# Sheet8.net
KiCad netlist of a schematic drawn in Altium Designer
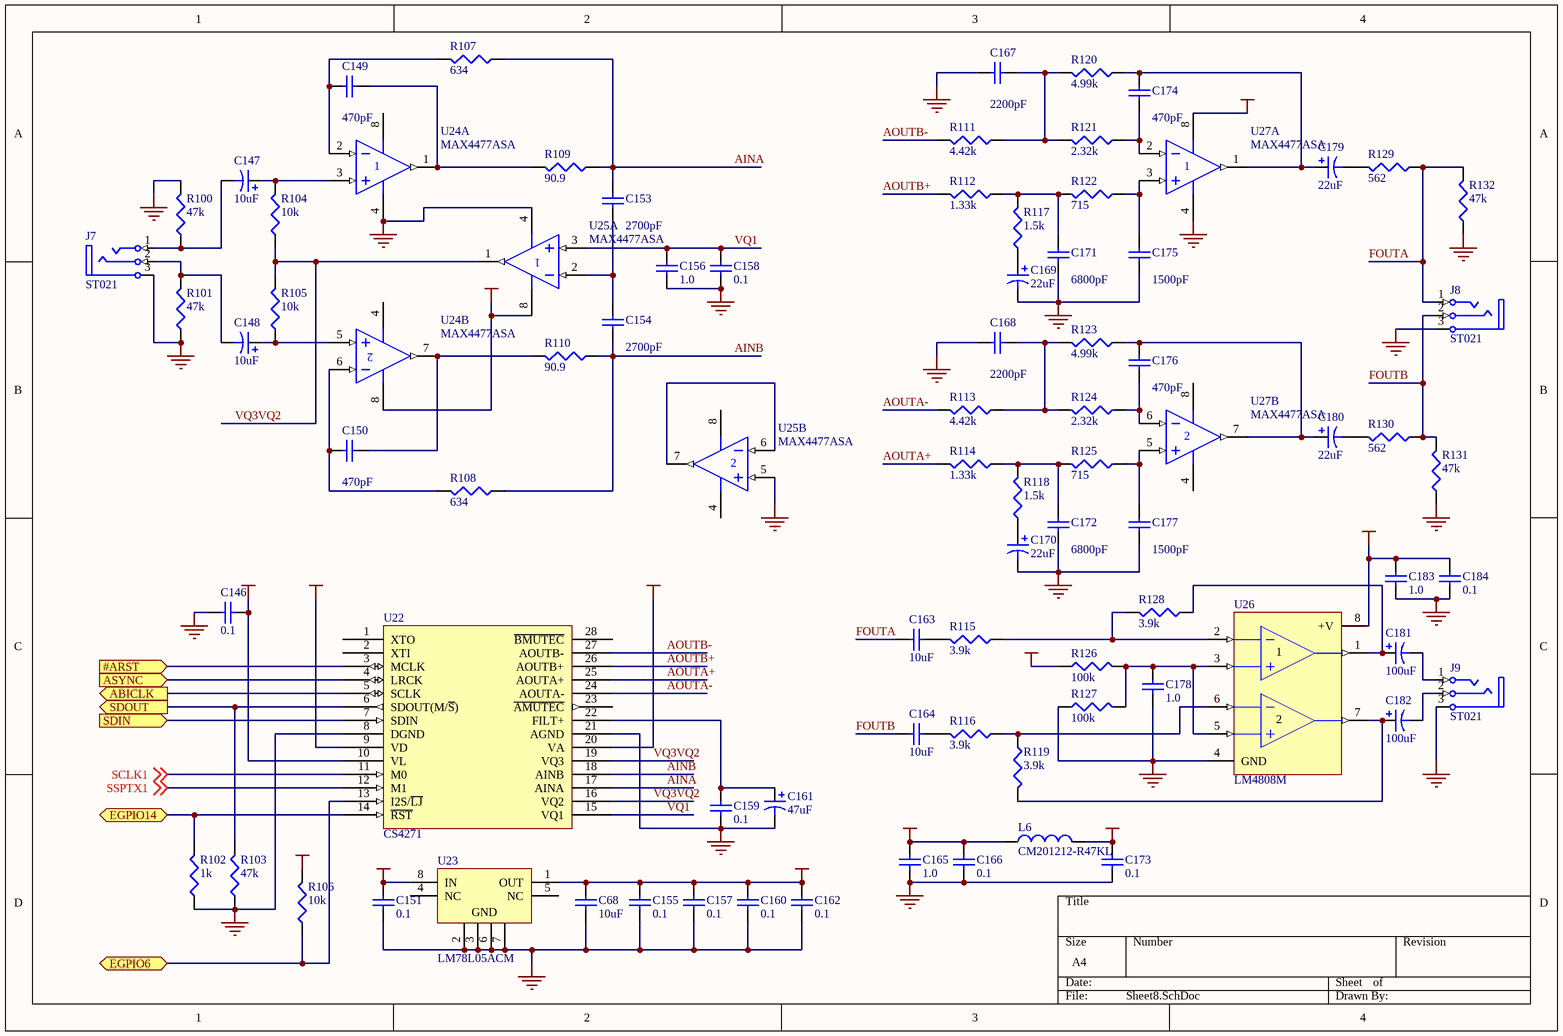
[diagram p0: Sheet8.SchDoc]

(export (version "E")
  (design (tool "Eeschema 10.0.6"))
  (components
    (comp (ref "C68")
      (value "10uF")
      (footprint "1206")
      (description "Ceramic Chip Capacitor - Standard")
      (fields (field (name "PUBLISHER") "Altium Limited"))
      (libsource (lib "KEMET Chip Capacitor") (part "C1206"))
    )
    (comp (ref "C146")
      (value "0.1")
      (footprint "0603")
      (description "Ceramic Chip Capacitor - Standard")
      (fields (field (name "PUBLISHER") "Altium Limited"))
      (libsource (lib "KEMET Chip Capacitor") (part "C0603"))
    )
    (comp (ref "C147")
      (value "10uF")
      (footprint "CAPPR1.5-4x5")
      (description "Polarized Capacitor (Radial)")
      (fields (field (name "PUBLISHER") "Altium Limited"))
      (libsource (lib "Miscellaneous Devices") (part "Cap Pol1"))
    )
    (comp (ref "C148")
      (value "10uF")
      (footprint "CAPPR1.5-4x5")
      (description "Polarized Capacitor (Radial)")
      (fields (field (name "PUBLISHER") "Altium Limited"))
      (libsource (lib "Miscellaneous Devices") (part "Cap Pol1"))
    )
    (comp (ref "C149")
      (value "470pF")
      (footprint "0603")
      (description "Ceramic Chip Capacitor - Standard")
      (fields (field (name "PUBLISHER") "Altium Limited"))
      (libsource (lib "KEMET Chip Capacitor") (part "C0603"))
    )
    (comp (ref "C150")
      (value "470pF")
      (footprint "0603")
      (description "Ceramic Chip Capacitor - Standard")
      (fields (field (name "PUBLISHER") "Altium Limited"))
      (libsource (lib "KEMET Chip Capacitor") (part "C0603"))
    )
    (comp (ref "C151")
      (value "0.1")
      (footprint "0603")
      (description "Ceramic Chip Capacitor - Standard")
      (fields (field (name "PUBLISHER") "Altium Limited"))
      (libsource (lib "KEMET Chip Capacitor") (part "C0603"))
    )
    (comp (ref "C153")
      (value "2700pF")
      (footprint "0603")
      (description "Ceramic Chip Capacitor - Standard")
      (fields (field (name "PUBLISHER") "Altium Limited"))
      (libsource (lib "KEMET Chip Capacitor") (part "C0603"))
    )
    (comp (ref "C154")
      (value "2700pF")
      (footprint "0603")
      (description "Ceramic Chip Capacitor - Standard")
      (fields (field (name "PUBLISHER") "Altium Limited"))
      (libsource (lib "KEMET Chip Capacitor") (part "C0603"))
    )
    (comp (ref "C155")
      (value "0.1")
      (footprint "0603")
      (description "Ceramic Chip Capacitor - Standard")
      (fields (field (name "PUBLISHER") "Altium Limited"))
      (libsource (lib "KEMET Chip Capacitor") (part "C0603"))
    )
    (comp (ref "C156")
      (value "1.0")
      (footprint "0603")
      (description "Ceramic Chip Capacitor - Standard")
      (fields (field (name "PUBLISHER") "Altium Limited"))
      (libsource (lib "KEMET Chip Capacitor") (part "C0603"))
    )
    (comp (ref "C157")
      (value "0.1")
      (footprint "0603")
      (description "Ceramic Chip Capacitor - Standard")
      (fields (field (name "PUBLISHER") "Altium Limited"))
      (libsource (lib "KEMET Chip Capacitor") (part "C0603"))
    )
    (comp (ref "C158")
      (value "0.1")
      (footprint "0603")
      (description "Ceramic Chip Capacitor - Standard")
      (fields (field (name "PUBLISHER") "Altium Limited"))
      (libsource (lib "KEMET Chip Capacitor") (part "C0603"))
    )
    (comp (ref "C159")
      (value "0.1")
      (footprint "0603")
      (description "Ceramic Chip Capacitor - Standard")
      (fields (field (name "PUBLISHER") "Altium Limited"))
      (libsource (lib "KEMET Chip Capacitor") (part "C0603"))
    )
    (comp (ref "C160")
      (value "0.1")
      (footprint "0603")
      (description "Ceramic Chip Capacitor - Standard")
      (fields (field (name "PUBLISHER") "Altium Limited"))
      (libsource (lib "KEMET Chip Capacitor") (part "C0603"))
    )
    (comp (ref "C161")
      (value "47uF")
      (footprint "CAPPR1.5-4x5")
      (description "Polarized Capacitor (Radial)")
      (fields (field (name "PUBLISHER") "Altium Limited"))
      (libsource (lib "Miscellaneous Devices") (part "Cap Pol1"))
    )
    (comp (ref "C162")
      (value "0.1")
      (footprint "0603")
      (description "Ceramic Chip Capacitor - Standard")
      (fields (field (name "PUBLISHER") "Altium Limited"))
      (libsource (lib "KEMET Chip Capacitor") (part "C0603"))
    )
    (comp (ref "C163")
      (value "10uF")
      (footprint "1206")
      (description "Ceramic Chip Capacitor - Standard")
      (fields (field (name "PUBLISHER") "Altium Limited"))
      (libsource (lib "KEMET Chip Capacitor") (part "C1206"))
    )
    (comp (ref "C164")
      (value "10uF")
      (footprint "1206")
      (description "Ceramic Chip Capacitor - Standard")
      (fields (field (name "PUBLISHER") "Altium Limited"))
      (libsource (lib "KEMET Chip Capacitor") (part "C1206"))
    )
    (comp (ref "C165")
      (value "1.0")
      (footprint "0603")
      (description "Ceramic Chip Capacitor - Standard")
      (fields (field (name "PUBLISHER") "Altium Limited"))
      (libsource (lib "KEMET Chip Capacitor") (part "C0603"))
    )
    (comp (ref "C166")
      (value "0.1")
      (footprint "0603")
      (description "Ceramic Chip Capacitor - Standard")
      (fields (field (name "PUBLISHER") "Altium Limited"))
      (libsource (lib "KEMET Chip Capacitor") (part "C0603"))
    )
    (comp (ref "C167")
      (value "2200pF")
      (footprint "0603")
      (description "Ceramic Chip Capacitor - Standard")
      (fields (field (name "PUBLISHER") "Altium Limited"))
      (libsource (lib "KEMET Chip Capacitor") (part "C0603"))
    )
    (comp (ref "C168")
      (value "2200pF")
      (footprint "0603")
      (description "Ceramic Chip Capacitor - Standard")
      (fields (field (name "PUBLISHER") "Altium Limited"))
      (libsource (lib "KEMET Chip Capacitor") (part "C0603"))
    )
    (comp (ref "C169")
      (value "22uF")
      (footprint "CAPPR1.5-4x5")
      (description "Polarized Capacitor (Radial)")
      (fields (field (name "PUBLISHER") "Altium Limited"))
      (libsource (lib "Miscellaneous Devices") (part "Cap Pol1"))
    )
    (comp (ref "C170")
      (value "22uF")
      (footprint "CAPPR1.5-4x5")
      (description "Polarized Capacitor (Radial)")
      (fields (field (name "PUBLISHER") "Altium Limited"))
      (libsource (lib "Miscellaneous Devices") (part "Cap Pol1"))
    )
    (comp (ref "C171")
      (value "6800pF")
      (footprint "0603")
      (description "Ceramic Chip Capacitor - Standard")
      (fields (field (name "PUBLISHER") "Altium Limited"))
      (libsource (lib "KEMET Chip Capacitor") (part "C0603"))
    )
    (comp (ref "C172")
      (value "6800pF")
      (footprint "0603")
      (description "Ceramic Chip Capacitor - Standard")
      (fields (field (name "PUBLISHER") "Altium Limited"))
      (libsource (lib "KEMET Chip Capacitor") (part "C0603"))
    )
    (comp (ref "C173")
      (value "0.1")
      (footprint "0603")
      (description "Ceramic Chip Capacitor - Standard")
      (fields (field (name "PUBLISHER") "Altium Limited"))
      (libsource (lib "KEMET Chip Capacitor") (part "C0603"))
    )
    (comp (ref "C174")
      (value "470pF")
      (footprint "0603")
      (description "Ceramic Chip Capacitor - Standard")
      (fields (field (name "PUBLISHER") "Altium Limited"))
      (libsource (lib "KEMET Chip Capacitor") (part "C0603"))
    )
    (comp (ref "C175")
      (value "1500pF")
      (footprint "0603")
      (description "Ceramic Chip Capacitor - Standard")
      (fields (field (name "PUBLISHER") "Altium Limited"))
      (libsource (lib "KEMET Chip Capacitor") (part "C0603"))
    )
    (comp (ref "C176")
      (value "470pF")
      (footprint "0603")
      (description "Ceramic Chip Capacitor - Standard")
      (fields (field (name "PUBLISHER") "Altium Limited"))
      (libsource (lib "KEMET Chip Capacitor") (part "C0603"))
    )
    (comp (ref "C177")
      (value "1500pF")
      (footprint "0603")
      (description "Ceramic Chip Capacitor - Standard")
      (fields (field (name "PUBLISHER") "Altium Limited"))
      (libsource (lib "KEMET Chip Capacitor") (part "C0603"))
    )
    (comp (ref "C178")
      (value "1.0")
      (footprint "0603")
      (description "Ceramic Chip Capacitor - Standard")
      (fields (field (name "PUBLISHER") "Altium Limited"))
      (libsource (lib "KEMET Chip Capacitor") (part "C0603"))
    )
    (comp (ref "C179")
      (value "22uF")
      (footprint "CAPPR1.5-4x5")
      (description "Polarized Capacitor (Radial)")
      (fields (field (name "PUBLISHER") "Altium Limited"))
      (libsource (lib "Miscellaneous Devices") (part "Cap Pol1"))
    )
    (comp (ref "C180")
      (value "22uF")
      (footprint "CAPPR1.5-4x5")
      (description "Polarized Capacitor (Radial)")
      (fields (field (name "PUBLISHER") "Altium Limited"))
      (libsource (lib "Miscellaneous Devices") (part "Cap Pol1"))
    )
    (comp (ref "C181")
      (value "100uF")
      (footprint "CAPPR1.5-4x5")
      (description "Polarized Capacitor (Radial)")
      (fields (field (name "PUBLISHER") "Altium Limited"))
      (libsource (lib "Miscellaneous Devices") (part "Cap Pol1"))
    )
    (comp (ref "C182")
      (value "100uF")
      (footprint "CAPPR1.5-4x5")
      (description "Polarized Capacitor (Radial)")
      (fields (field (name "PUBLISHER") "Altium Limited"))
      (libsource (lib "Miscellaneous Devices") (part "Cap Pol1"))
    )
    (comp (ref "C183")
      (value "1.0")
      (footprint "0603")
      (description "Ceramic Chip Capacitor - Standard")
      (fields (field (name "PUBLISHER") "Altium Limited"))
      (libsource (lib "KEMET Chip Capacitor") (part "C0603"))
    )
    (comp (ref "C184")
      (value "0.1")
      (footprint "0603")
      (description "Ceramic Chip Capacitor - Standard")
      (fields (field (name "PUBLISHER") "Altium Limited"))
      (libsource (lib "KEMET Chip Capacitor") (part "C0603"))
    )
    (comp (ref "J7")
      (value "ST021")
      (footprint "ST023")
      (description "3.5\" jack")
      (libsource (lib "*") (part "PhoneJack"))
    )
    (comp (ref "J8")
      (value "ST021")
      (footprint "ST023")
      (description "3.5\" jack")
      (libsource (lib "*") (part "PhoneJack"))
    )
    (comp (ref "J9")
      (value "ST021")
      (footprint "ST023")
      (description "3.5\" jack")
      (libsource (lib "*") (part "PhoneJack"))
    )
    (comp (ref "L6")
      (value "CM201212-R47KL")
      (footprint "INDC2012-0805")
      (description "Inductor")
      (fields (field (name "PUBLISHER") "Altium Limited"))
      (libsource (lib "Miscellaneous Devices") (part "Inductor"))
    )
    (comp (ref "R100")
      (value "47k")
      (footprint "CR1608-0603")
      (description "Resistor")
      (fields (field (name "PUBLISHER") "Altium Limited"))
      (libsource (lib "Miscellaneous Devices") (part "Res3"))
    )
    (comp (ref "R101")
      (value "47k")
      (footprint "CR1608-0603")
      (description "Resistor")
      (fields (field (name "PUBLISHER") "Altium Limited"))
      (libsource (lib "Miscellaneous Devices") (part "Res3"))
    )
    (comp (ref "R102")
      (value "1k")
      (footprint "CR1608-0603")
      (description "Resistor")
      (fields (field (name "PUBLISHER") "Altium Limited"))
      (libsource (lib "Miscellaneous Devices") (part "Res3"))
    )
    (comp (ref "R103")
      (value "47k")
      (footprint "CR1608-0603")
      (description "Resistor")
      (fields (field (name "PUBLISHER") "Altium Limited"))
      (libsource (lib "Miscellaneous Devices") (part "Res3"))
    )
    (comp (ref "R104")
      (value "10k")
      (footprint "CR1608-0603")
      (description "Resistor")
      (fields (field (name "PUBLISHER") "Altium Limited"))
      (libsource (lib "Miscellaneous Devices") (part "Res3"))
    )
    (comp (ref "R105")
      (value "10k")
      (footprint "CR1608-0603")
      (description "Resistor")
      (fields (field (name "PUBLISHER") "Altium Limited"))
      (libsource (lib "Miscellaneous Devices") (part "Res3"))
    )
    (comp (ref "R106")
      (value "10k")
      (footprint "CR1608-0603")
      (description "Resistor")
      (fields (field (name "PUBLISHER") "Altium Limited"))
      (libsource (lib "Miscellaneous Devices") (part "Res3"))
    )
    (comp (ref "R107")
      (value "634")
      (footprint "CR1608-0603")
      (description "Resistor")
      (fields (field (name "PUBLISHER") "Altium Limited"))
      (libsource (lib "Miscellaneous Devices") (part "Res3"))
    )
    (comp (ref "R108")
      (value "634")
      (footprint "CR1608-0603")
      (description "Resistor")
      (fields (field (name "PUBLISHER") "Altium Limited"))
      (libsource (lib "Miscellaneous Devices") (part "Res3"))
    )
    (comp (ref "R109")
      (value "90.9")
      (footprint "CR1608-0603")
      (description "Resistor")
      (fields (field (name "PUBLISHER") "Altium Limited"))
      (libsource (lib "Miscellaneous Devices") (part "Res3"))
    )
    (comp (ref "R110")
      (value "90.9")
      (footprint "CR1608-0603")
      (description "Resistor")
      (fields (field (name "PUBLISHER") "Altium Limited"))
      (libsource (lib "Miscellaneous Devices") (part "Res3"))
    )
    (comp (ref "R111")
      (value "4.42k")
      (footprint "CR1608-0603")
      (description "Resistor")
      (fields (field (name "PUBLISHER") "Altium Limited"))
      (libsource (lib "Miscellaneous Devices") (part "Res3"))
    )
    (comp (ref "R112")
      (value "1.33k")
      (footprint "CR1608-0603")
      (description "Resistor")
      (fields (field (name "PUBLISHER") "Altium Limited"))
      (libsource (lib "Miscellaneous Devices") (part "Res3"))
    )
    (comp (ref "R113")
      (value "4.42k")
      (footprint "CR1608-0603")
      (description "Resistor")
      (fields (field (name "PUBLISHER") "Altium Limited"))
      (libsource (lib "Miscellaneous Devices") (part "Res3"))
    )
    (comp (ref "R114")
      (value "1.33k")
      (footprint "CR1608-0603")
      (description "Resistor")
      (fields (field (name "PUBLISHER") "Altium Limited"))
      (libsource (lib "Miscellaneous Devices") (part "Res3"))
    )
    (comp (ref "R115")
      (value "3.9k")
      (footprint "CR1608-0603")
      (description "Resistor")
      (fields (field (name "PUBLISHER") "Altium Limited"))
      (libsource (lib "Miscellaneous Devices") (part "Res3"))
    )
    (comp (ref "R116")
      (value "3.9k")
      (footprint "CR1608-0603")
      (description "Resistor")
      (fields (field (name "PUBLISHER") "Altium Limited"))
      (libsource (lib "Miscellaneous Devices") (part "Res3"))
    )
    (comp (ref "R117")
      (value "1.5k")
      (footprint "CR1608-0603")
      (description "Resistor")
      (fields (field (name "PUBLISHER") "Altium Limited"))
      (libsource (lib "Miscellaneous Devices") (part "Res3"))
    )
    (comp (ref "R118")
      (value "1.5k")
      (footprint "CR1608-0603")
      (description "Resistor")
      (fields (field (name "PUBLISHER") "Altium Limited"))
      (libsource (lib "Miscellaneous Devices") (part "Res3"))
    )
    (comp (ref "R119")
      (value "3.9k")
      (footprint "CR1608-0603")
      (description "Resistor")
      (fields (field (name "PUBLISHER") "Altium Limited"))
      (libsource (lib "Miscellaneous Devices") (part "Res3"))
    )
    (comp (ref "R120")
      (value "4.99k")
      (footprint "CR1608-0603")
      (description "Resistor")
      (fields (field (name "PUBLISHER") "Altium Limited"))
      (libsource (lib "Miscellaneous Devices") (part "Res3"))
    )
    (comp (ref "R121")
      (value "2.32k")
      (footprint "CR1608-0603")
      (description "Resistor")
      (fields (field (name "PUBLISHER") "Altium Limited"))
      (libsource (lib "Miscellaneous Devices") (part "Res3"))
    )
    (comp (ref "R122")
      (value "715")
      (footprint "CR1608-0603")
      (description "Resistor")
      (fields (field (name "PUBLISHER") "Altium Limited"))
      (libsource (lib "Miscellaneous Devices") (part "Res3"))
    )
    (comp (ref "R123")
      (value "4.99k")
      (footprint "CR1608-0603")
      (description "Resistor")
      (fields (field (name "PUBLISHER") "Altium Limited"))
      (libsource (lib "Miscellaneous Devices") (part "Res3"))
    )
    (comp (ref "R124")
      (value "2.32k")
      (footprint "CR1608-0603")
      (description "Resistor")
      (fields (field (name "PUBLISHER") "Altium Limited"))
      (libsource (lib "Miscellaneous Devices") (part "Res3"))
    )
    (comp (ref "R125")
      (value "715")
      (footprint "CR1608-0603")
      (description "Resistor")
      (fields (field (name "PUBLISHER") "Altium Limited"))
      (libsource (lib "Miscellaneous Devices") (part "Res3"))
    )
    (comp (ref "R126")
      (value "100k")
      (footprint "CR1608-0603")
      (description "Resistor")
      (fields (field (name "PUBLISHER") "Altium Limited"))
      (libsource (lib "Miscellaneous Devices") (part "Res3"))
    )
    (comp (ref "R127")
      (value "100k")
      (footprint "CR1608-0603")
      (description "Resistor")
      (fields (field (name "PUBLISHER") "Altium Limited"))
      (libsource (lib "Miscellaneous Devices") (part "Res3"))
    )
    (comp (ref "R128")
      (value "3.9k")
      (footprint "CR1608-0603")
      (description "Resistor")
      (fields (field (name "PUBLISHER") "Altium Limited"))
      (libsource (lib "Miscellaneous Devices") (part "Res3"))
    )
    (comp (ref "R129")
      (value "562")
      (footprint "CR1608-0603")
      (description "Resistor")
      (fields (field (name "PUBLISHER") "Altium Limited"))
      (libsource (lib "Miscellaneous Devices") (part "Res3"))
    )
    (comp (ref "R130")
      (value "562")
      (footprint "CR1608-0603")
      (description "Resistor")
      (fields (field (name "PUBLISHER") "Altium Limited"))
      (libsource (lib "Miscellaneous Devices") (part "Res3"))
    )
    (comp (ref "R131")
      (value "47k")
      (footprint "CR1608-0603")
      (description "Resistor")
      (fields (field (name "PUBLISHER") "Altium Limited"))
      (libsource (lib "Miscellaneous Devices") (part "Res3"))
    )
    (comp (ref "R132")
      (value "47k")
      (footprint "CR1608-0603")
      (description "Resistor")
      (fields (field (name "PUBLISHER") "Altium Limited"))
      (libsource (lib "Miscellaneous Devices") (part "Res3"))
    )
    (comp (ref "U22")
      (value "CS4271")
      (footprint "TSOP28")
      (description "24-Bit, 192 kHz Stereo Audio CODEC")
      (libsource (lib "CS4271") (part "CS4271"))
    )
    (comp (ref "U23")
      (value "LM78L05ACM")
      (footprint "M08A")
      (description "3-Terminal Positive Regulator")
      (fields (field (name "PUBLISHER") "Altium Limited"))
      (libsource (lib "NSC Power Mgt Voltage Regulator") (part "LM78L05ACM"))
    )
    (comp (ref "U24")
      (value "MAX4477ASA")
      (footprint "NSO8")
      (description "Dual, +1.8V/10µA, SOT23, Beyond-the-Rails Op Amp")
      (fields (field (name "PUBLISHER") "Altium Limited"))
      (libsource (lib "Maxim Operational Amplifier") (part "MAX4242ESA"))
    )
    (comp (ref "U25")
      (value "MAX4477ASA")
      (footprint "NSO8")
      (description "Dual, +1.8V/10µA, SOT23, Beyond-the-Rails Op Amp")
      (fields (field (name "PUBLISHER") "Altium Limited"))
      (libsource (lib "Maxim Operational Amplifier") (part "MAX4242ESA"))
    )
    (comp (ref "U26")
      (value "LM4808M")
      (footprint "M08A")
      (description "Dual 105 mW Headphone Amplifier")
      (libsource (lib "*") (part "LM4808M"))
    )
    (comp (ref "U27")
      (value "MAX4477ASA")
      (footprint "NSO8")
      (description "Dual, +1.8V/10µA, SOT23, Beyond-the-Rails Op Amp")
      (fields (field (name "PUBLISHER") "Altium Limited"))
      (libsource (lib "Maxim Operational Amplifier") (part "MAX4242ESA"))
    )
  )
  (nets
    (net (code "1") (name "/#ARST") (class "Default")
      (node (ref "U22") (pin "3") (pinfunction "MCLK_3") (pintype "bidirectional"))
    )
    (net (code "2") (name "/ABICLK") (class "Default")
      (node (ref "U22") (pin "5") (pinfunction "SCLK_5") (pintype "bidirectional"))
    )
    (net (code "3") (name "/AINA") (class "Default")
      (node (ref "C153") (pin "2") (pinfunction "2_2") (pintype "passive"))
      (node (ref "R107") (pin "1") (pinfunction "1_1") (pintype "passive"))
      (node (ref "R109") (pin "1") (pinfunction "1_1") (pintype "passive"))
      (node (ref "U22") (pin "17") (pinfunction "AINA_17") (pintype "passive"))
    )
    (net (code "4") (name "/AINB") (class "Default")
      (node (ref "C154") (pin "1") (pinfunction "1_1") (pintype "passive"))
      (node (ref "R108") (pin "1") (pinfunction "1_1") (pintype "passive"))
      (node (ref "R110") (pin "1") (pinfunction "1_1") (pintype "passive"))
      (node (ref "U22") (pin "18") (pinfunction "AINB_18") (pintype "passive"))
    )
    (net (code "5") (name "/AOUTA+") (class "Default")
      (node (ref "R114") (pin "2") (pinfunction "2_2") (pintype "passive"))
      (node (ref "U22") (pin "25") (pinfunction "AOUTA+_25") (pintype "passive"))
    )
    (net (code "6") (name "/AOUTA-") (class "Default")
      (node (ref "R113") (pin "2") (pinfunction "2_2") (pintype "passive"))
      (node (ref "U22") (pin "24") (pinfunction "AOUTA-_24") (pintype "passive"))
    )
    (net (code "7") (name "/AOUTB+") (class "Default")
      (node (ref "R112") (pin "2") (pinfunction "2_2") (pintype "passive"))
      (node (ref "U22") (pin "26") (pinfunction "AOUTB+_26") (pintype "passive"))
    )
    (net (code "8") (name "/AOUTB-") (class "Default")
      (node (ref "R111") (pin "2") (pinfunction "2_2") (pintype "passive"))
      (node (ref "U22") (pin "27") (pinfunction "AOUTB-_27") (pintype "passive"))
    )
    (net (code "9") (name "/ASYNC") (class "Default")
      (node (ref "U22") (pin "4") (pinfunction "LRCK_4") (pintype "bidirectional"))
    )
    (net (code "10") (name "/EGPIO6") (class "Default")
      (node (ref "R106") (pin "1") (pinfunction "1_1") (pintype "passive"))
      (node (ref "U22") (pin "13") (pinfunction "I2S/~{LJ}_13") (pintype "input"))
    )
    (net (code "11") (name "/EGPIO14") (class "Default")
      (node (ref "R102") (pin "2") (pinfunction "2_2") (pintype "passive"))
      (node (ref "U22") (pin "14") (pinfunction "~{RST}_14") (pintype "input"))
    )
    (net (code "12") (name "/FOUTA") (class "Default")
      (node (ref "C163") (pin "2") (pinfunction "2_2") (pintype "passive"))
      (node (ref "J8") (pin "1") (pinfunction "T_1") (pintype "input"))
      (node (ref "R129") (pin "1") (pinfunction "1_1") (pintype "passive"))
      (node (ref "R132") (pin "2") (pinfunction "2_2") (pintype "passive"))
    )
    (net (code "13") (name "/FOUTB") (class "Default")
      (node (ref "C164") (pin "2") (pinfunction "2_2") (pintype "passive"))
      (node (ref "J8") (pin "2") (pinfunction "R_2") (pintype "input"))
      (node (ref "R130") (pin "1") (pinfunction "1_1") (pintype "passive"))
      (node (ref "R131") (pin "2") (pinfunction "2_2") (pintype "passive"))
    )
    (net (code "14") (name "/SDIN") (class "Default")
      (node (ref "U22") (pin "7") (pinfunction "SDIN_7") (pintype "input"))
    )
    (net (code "15") (name "/SDOUT") (class "Default")
      (node (ref "R103") (pin "2") (pinfunction "2_2") (pintype "passive"))
      (node (ref "U22") (pin "6") (pinfunction "SDOUT(M/~{S})_6") (pintype "output"))
    )
    (net (code "16") (name "/VQ1") (class "Default")
      (node (ref "C156") (pin "2") (pinfunction "2_2") (pintype "passive"))
      (node (ref "C158") (pin "2") (pinfunction "2_2") (pintype "passive"))
      (node (ref "U22") (pin "15") (pinfunction "VQ1_15") (pintype "passive"))
      (node (ref "U25") (pin "3") (pinfunction "IN+_3") (pintype "input"))
    )
    (net (code "17") (name "/VQ3VQ2") (class "Default")
      (node (ref "R104") (pin "1") (pinfunction "1_1") (pintype "passive"))
      (node (ref "R105") (pin "2") (pinfunction "2_2") (pintype "passive"))
      (node (ref "U22") (pin "16") (pinfunction "VQ2_16") (pintype "passive"))
      (node (ref "U22") (pin "19") (pinfunction "VQ3_19") (pintype "passive"))
      (node (ref "U25") (pin "1") (pinfunction "OUT_1") (pintype "output"))
    )
    (net (code "18") (name "GND") (class "Default")
      (node (ref "C146") (pin "1") (pinfunction "1_1") (pintype "passive"))
      (node (ref "C151") (pin "2") (pinfunction "2_2") (pintype "passive"))
      (node (ref "C155") (pin "2") (pinfunction "2_2") (pintype "passive"))
      (node (ref "C156") (pin "1") (pinfunction "1_1") (pintype "passive"))
      (node (ref "C157") (pin "2") (pinfunction "2_2") (pintype "passive"))
      (node (ref "C158") (pin "1") (pinfunction "1_1") (pintype "passive"))
      (node (ref "C159") (pin "2") (pinfunction "2_2") (pintype "passive"))
      (node (ref "C160") (pin "2") (pinfunction "2_2") (pintype "passive"))
      (node (ref "C161") (pin "2") (pinfunction "2_2") (pintype "passive"))
      (node (ref "C162") (pin "2") (pinfunction "2_2") (pintype "passive"))
      (node (ref "C165") (pin "1") (pinfunction "1_1") (pintype "passive"))
      (node (ref "C166") (pin "2") (pinfunction "2_2") (pintype "passive"))
      (node (ref "C167") (pin "2") (pinfunction "2_2") (pintype "passive"))
      (node (ref "C168") (pin "2") (pinfunction "2_2") (pintype "passive"))
      (node (ref "C169") (pin "2") (pinfunction "2_2") (pintype "passive"))
      (node (ref "C170") (pin "2") (pinfunction "2_2") (pintype "passive"))
      (node (ref "C171") (pin "1") (pinfunction "1_1") (pintype "passive"))
      (node (ref "C172") (pin "1") (pinfunction "1_1") (pintype "passive"))
      (node (ref "C173") (pin "2") (pinfunction "2_2") (pintype "passive"))
      (node (ref "C175") (pin "1") (pinfunction "1_1") (pintype "passive"))
      (node (ref "C177") (pin "1") (pinfunction "1_1") (pintype "passive"))
      (node (ref "C178") (pin "1") (pinfunction "1_1") (pintype "passive"))
      (node (ref "C183") (pin "1") (pinfunction "1_1") (pintype "passive"))
      (node (ref "C184") (pin "2") (pinfunction "2_2") (pintype "passive"))
      (node (ref "C68") (pin "1") (pinfunction "1_1") (pintype "passive"))
      (node (ref "J7") (pin "3") (pinfunction "S_3") (pintype "power_in"))
      (node (ref "J8") (pin "3") (pinfunction "S_3") (pintype "power_in"))
      (node (ref "J9") (pin "3") (pinfunction "S_3") (pintype "power_in"))
      (node (ref "R100") (pin "2") (pinfunction "2_2") (pintype "passive"))
      (node (ref "R101") (pin "1") (pinfunction "1_1") (pintype "passive"))
      (node (ref "R102") (pin "1") (pinfunction "1_1") (pintype "passive"))
      (node (ref "R103") (pin "1") (pinfunction "1_1") (pintype "passive"))
      (node (ref "R127") (pin "1") (pinfunction "1_1") (pintype "passive"))
      (node (ref "R131") (pin "1") (pinfunction "1_1") (pintype "passive"))
      (node (ref "R132") (pin "1") (pinfunction "1_1") (pintype "passive"))
      (node (ref "U22") (pin "21") (pinfunction "AGND_21") (pintype "passive"))
      (node (ref "U22") (pin "8") (pinfunction "DGND_8") (pintype "passive"))
      (node (ref "U23") (pin "2") (pinfunction "GND_2") (pintype "power_in"))
      (node (ref "U23") (pin "3") (pinfunction "GND_3") (pintype "power_in"))
      (node (ref "U23") (pin "6") (pinfunction "GND_6") (pintype "power_in"))
      (node (ref "U23") (pin "7") (pinfunction "GND_7") (pintype "power_in"))
      (node (ref "U24") (pin "4") (pinfunction "VEE_4") (pintype "power_in"))
      (node (ref "U25") (pin "4") (pinfunction "VEE_4") (pintype "power_in"))
      (node (ref "U25") (pin "5") (pinfunction "IN+_5") (pintype "input"))
      (node (ref "U26") (pin "4") (pinfunction "GND_4") (pintype "power_in"))
      (node (ref "U27") (pin "4") (pinfunction "VEE_4") (pintype "power_in"))
    )
    (net (code "19") (name "Net-(C163-Pad1)") (class "Default")
      (node (ref "C163") (pin "1") (pinfunction "1_1") (pintype "passive"))
      (node (ref "R115") (pin "2") (pinfunction "2_2") (pintype "passive"))
    )
    (net (code "20") (name "Net-(C164-Pad1)") (class "Default")
      (node (ref "C164") (pin "1") (pinfunction "1_1") (pintype "passive"))
      (node (ref "R116") (pin "2") (pinfunction "2_2") (pintype "passive"))
    )
    (net (code "21") (name "Net-(C167-Pad1)") (class "Default")
      (node (ref "C167") (pin "1") (pinfunction "1_1") (pintype "passive"))
      (node (ref "R111") (pin "1") (pinfunction "1_1") (pintype "passive"))
      (node (ref "R120") (pin "2") (pinfunction "2_2") (pintype "passive"))
      (node (ref "R121") (pin "2") (pinfunction "2_2") (pintype "passive"))
    )
    (net (code "22") (name "Net-(C168-Pad1)") (class "Default")
      (node (ref "C168") (pin "1") (pinfunction "1_1") (pintype "passive"))
      (node (ref "R113") (pin "1") (pinfunction "1_1") (pintype "passive"))
      (node (ref "R123") (pin "2") (pinfunction "2_2") (pintype "passive"))
      (node (ref "R124") (pin "2") (pinfunction "2_2") (pintype "passive"))
    )
    (net (code "23") (name "Net-(C169-Pad1)") (class "Default")
      (node (ref "C169") (pin "1") (pinfunction "1_1") (pintype "passive"))
      (node (ref "R117") (pin "1") (pinfunction "1_1") (pintype "passive"))
    )
    (net (code "24") (name "Net-(C170-Pad1)") (class "Default")
      (node (ref "C170") (pin "1") (pinfunction "1_1") (pintype "passive"))
      (node (ref "R118") (pin "1") (pinfunction "1_1") (pintype "passive"))
    )
    (net (code "25") (name "Net-(C171-Pad2)") (class "Default")
      (node (ref "C171") (pin "2") (pinfunction "2_2") (pintype "passive"))
      (node (ref "R112") (pin "1") (pinfunction "1_1") (pintype "passive"))
      (node (ref "R117") (pin "2") (pinfunction "2_2") (pintype "passive"))
      (node (ref "R122") (pin "2") (pinfunction "2_2") (pintype "passive"))
    )
    (net (code "26") (name "Net-(C172-Pad2)") (class "Default")
      (node (ref "C172") (pin "2") (pinfunction "2_2") (pintype "passive"))
      (node (ref "R114") (pin "1") (pinfunction "1_1") (pintype "passive"))
      (node (ref "R118") (pin "2") (pinfunction "2_2") (pintype "passive"))
      (node (ref "R125") (pin "2") (pinfunction "2_2") (pintype "passive"))
    )
    (net (code "27") (name "Net-(C178-Pad2)") (class "Default")
      (node (ref "C178") (pin "2") (pinfunction "2_2") (pintype "passive"))
      (node (ref "R126") (pin "2") (pinfunction "2_2") (pintype "passive"))
      (node (ref "R127") (pin "2") (pinfunction "2_2") (pintype "passive"))
      (node (ref "U26") (pin "3") (pinfunction "IN+_3") (pintype "input"))
      (node (ref "U26") (pin "5") (pinfunction "IN+_5") (pintype "input"))
    )
    (net (code "28") (name "Net-(C179-Pad2)") (class "Default")
      (node (ref "C179") (pin "2") (pinfunction "2_2") (pintype "passive"))
      (node (ref "R129") (pin "2") (pinfunction "2_2") (pintype "passive"))
    )
    (net (code "29") (name "Net-(C180-Pad2)") (class "Default")
      (node (ref "C180") (pin "2") (pinfunction "2_2") (pintype "passive"))
      (node (ref "R130") (pin "2") (pinfunction "2_2") (pintype "passive"))
    )
    (net (code "30") (name "Net-(C181-Pad1)") (class "Default")
      (node (ref "C181") (pin "1") (pinfunction "1_1") (pintype "passive"))
      (node (ref "R128") (pin "1") (pinfunction "1_1") (pintype "passive"))
      (node (ref "U26") (pin "1") (pinfunction "OUT_1") (pintype "output"))
    )
    (net (code "31") (name "Net-(C182-Pad1)") (class "Default")
      (node (ref "C182") (pin "1") (pinfunction "1_1") (pintype "passive"))
      (node (ref "R119") (pin "2") (pinfunction "2_2") (pintype "passive"))
      (node (ref "U26") (pin "7") (pinfunction "OUT_7") (pintype "output"))
    )
    (net (code "32") (name "Net-(J7-R)") (class "Default")
      (node (ref "C148") (pin "2") (pinfunction "2_2") (pintype "passive"))
      (node (ref "J7") (pin "2") (pinfunction "R_2") (pintype "input"))
      (node (ref "R101") (pin "2") (pinfunction "2_2") (pintype "passive"))
    )
    (net (code "33") (name "Net-(J7-T)") (class "Default")
      (node (ref "C147") (pin "2") (pinfunction "2_2") (pintype "passive"))
      (node (ref "J7") (pin "1") (pinfunction "T_1") (pintype "input"))
      (node (ref "R100") (pin "1") (pinfunction "1_1") (pintype "passive"))
    )
    (net (code "34") (name "Net-(J9-R)") (class "Default")
      (node (ref "C182") (pin "2") (pinfunction "2_2") (pintype "passive"))
      (node (ref "J9") (pin "2") (pinfunction "R_2") (pintype "input"))
    )
    (net (code "35") (name "Net-(J9-T)") (class "Default")
      (node (ref "C181") (pin "2") (pinfunction "2_2") (pintype "passive"))
      (node (ref "J9") (pin "1") (pinfunction "T_1") (pintype "input"))
    )
    (net (code "36") (name "Net-(R115-Pad1)") (class "Default")
      (node (ref "R115") (pin "1") (pinfunction "1_1") (pintype "passive"))
      (node (ref "R128") (pin "2") (pinfunction "2_2") (pintype "passive"))
      (node (ref "U26") (pin "2") (pinfunction "IN-_2") (pintype "input"))
    )
    (net (code "37") (name "Net-(R116-Pad1)") (class "Default")
      (node (ref "R116") (pin "1") (pinfunction "1_1") (pintype "passive"))
      (node (ref "R119") (pin "1") (pinfunction "1_1") (pintype "passive"))
      (node (ref "U26") (pin "6") (pinfunction "IN-_6") (pintype "input"))
    )
    (net (code "38") (name "Net-(U22-FILT+)") (class "Default")
      (node (ref "C159") (pin "1") (pinfunction "1_1") (pintype "passive"))
      (node (ref "C161") (pin "1") (pinfunction "1_1") (pintype "passive"))
      (node (ref "U22") (pin "22") (pinfunction "FILT+_22") (pintype "passive"))
    )
    (net (code "39") (name "Net-(U24A-IN+)") (class "Default")
      (node (ref "C147") (pin "1") (pinfunction "1_1") (pintype "passive"))
      (node (ref "R104") (pin "2") (pinfunction "2_2") (pintype "passive"))
      (node (ref "U24") (pin "3") (pinfunction "IN+_3") (pintype "input"))
    )
    (net (code "40") (name "Net-(U24A-IN-)") (class "Default")
      (node (ref "C149") (pin "1") (pinfunction "1_1") (pintype "passive"))
      (node (ref "R107") (pin "2") (pinfunction "2_2") (pintype "passive"))
      (node (ref "U24") (pin "2") (pinfunction "IN-_2") (pintype "input"))
    )
    (net (code "41") (name "Net-(U24A-OUT)") (class "Default")
      (node (ref "C149") (pin "2") (pinfunction "2_2") (pintype "passive"))
      (node (ref "R109") (pin "2") (pinfunction "2_2") (pintype "passive"))
      (node (ref "U24") (pin "1") (pinfunction "OUT_1") (pintype "output"))
    )
    (net (code "42") (name "Net-(U24B-IN+)") (class "Default")
      (node (ref "C148") (pin "1") (pinfunction "1_1") (pintype "passive"))
      (node (ref "R105") (pin "1") (pinfunction "1_1") (pintype "passive"))
      (node (ref "U24") (pin "5") (pinfunction "IN+_5") (pintype "input"))
    )
    (net (code "43") (name "Net-(U24B-IN-)") (class "Default")
      (node (ref "C150") (pin "1") (pinfunction "1_1") (pintype "passive"))
      (node (ref "R108") (pin "2") (pinfunction "2_2") (pintype "passive"))
      (node (ref "U24") (pin "6") (pinfunction "IN-_6") (pintype "input"))
    )
    (net (code "44") (name "Net-(U24B-OUT)") (class "Default")
      (node (ref "C150") (pin "2") (pinfunction "2_2") (pintype "passive"))
      (node (ref "R110") (pin "2") (pinfunction "2_2") (pintype "passive"))
      (node (ref "U24") (pin "7") (pinfunction "OUT_7") (pintype "output"))
    )
    (net (code "45") (name "Net-(U25A-IN-)") (class "Default")
      (node (ref "C153") (pin "1") (pinfunction "1_1") (pintype "passive"))
      (node (ref "C154") (pin "2") (pinfunction "2_2") (pintype "passive"))
      (node (ref "U25") (pin "2") (pinfunction "IN-_2") (pintype "input"))
    )
    (net (code "46") (name "Net-(U25B-IN-)") (class "Default")
      (node (ref "U25") (pin "6") (pinfunction "IN-_6") (pintype "input"))
      (node (ref "U25") (pin "7") (pinfunction "OUT_7") (pintype "output"))
    )
    (net (code "47") (name "Net-(U27A-IN+)") (class "Default")
      (node (ref "C175") (pin "2") (pinfunction "2_2") (pintype "passive"))
      (node (ref "R122") (pin "1") (pinfunction "1_1") (pintype "passive"))
      (node (ref "U27") (pin "3") (pinfunction "IN+_3") (pintype "input"))
    )
    (net (code "48") (name "Net-(U27A-IN-)") (class "Default")
      (node (ref "C174") (pin "1") (pinfunction "1_1") (pintype "passive"))
      (node (ref "R121") (pin "1") (pinfunction "1_1") (pintype "passive"))
      (node (ref "U27") (pin "2") (pinfunction "IN-_2") (pintype "input"))
    )
    (net (code "49") (name "Net-(U27A-OUT)") (class "Default")
      (node (ref "C174") (pin "2") (pinfunction "2_2") (pintype "passive"))
      (node (ref "C179") (pin "1") (pinfunction "1_1") (pintype "passive"))
      (node (ref "R120") (pin "1") (pinfunction "1_1") (pintype "passive"))
      (node (ref "U27") (pin "1") (pinfunction "OUT_1") (pintype "output"))
    )
    (net (code "50") (name "Net-(U27B-IN+)") (class "Default")
      (node (ref "C177") (pin "2") (pinfunction "2_2") (pintype "passive"))
      (node (ref "R125") (pin "1") (pinfunction "1_1") (pintype "passive"))
      (node (ref "U27") (pin "5") (pinfunction "IN+_5") (pintype "input"))
    )
    (net (code "51") (name "Net-(U27B-IN-)") (class "Default")
      (node (ref "C176") (pin "1") (pinfunction "1_1") (pintype "passive"))
      (node (ref "R124") (pin "1") (pinfunction "1_1") (pintype "passive"))
      (node (ref "U27") (pin "6") (pinfunction "IN-_6") (pintype "input"))
    )
    (net (code "52") (name "Net-(U27B-OUT)") (class "Default")
      (node (ref "C176") (pin "2") (pinfunction "2_2") (pintype "passive"))
      (node (ref "C180") (pin "1") (pinfunction "1_1") (pintype "passive"))
      (node (ref "R123") (pin "1") (pinfunction "1_1") (pintype "passive"))
      (node (ref "U27") (pin "7") (pinfunction "OUT_7") (pintype "output"))
    )
    (net (code "53") (name "SCLK1") (class "Default")
      (node (ref "U22") (pin "11") (pinfunction "M0_11") (pintype "input"))
    )
    (net (code "54") (name "SSPTX1") (class "Default")
      (node (ref "U22") (pin "12") (pinfunction "M1_12") (pintype "input"))
    )
    (net (code "55") (name "VCC5V0") (class "Default")
      (node (ref "C173") (pin "1") (pinfunction "1_1") (pintype "passive"))
      (node (ref "L6") (pin "2") (pinfunction "2_2") (pintype "passive"))
    )
    (net (code "56") (name "VCC12") (class "Default")
      (node (ref "C151") (pin "1") (pinfunction "1_1") (pintype "passive"))
      (node (ref "U23") (pin "8") (pinfunction "IN_8") (pintype "power_in"))
    )
    (net (code "57") (name "VCCIO") (class "Default")
      (node (ref "C146") (pin "2") (pinfunction "2_2") (pintype "passive"))
      (node (ref "R106") (pin "2") (pinfunction "2_2") (pintype "passive"))
      (node (ref "U22") (pin "10") (pinfunction "VL_10") (pintype "passive"))
    )
    (net (code "58") (name "VCC_5V0_AD") (class "Default")
      (node (ref "C155") (pin "1") (pinfunction "1_1") (pintype "passive"))
      (node (ref "C157") (pin "1") (pinfunction "1_1") (pintype "passive"))
      (node (ref "C160") (pin "1") (pinfunction "1_1") (pintype "passive"))
      (node (ref "C162") (pin "1") (pinfunction "1_1") (pintype "passive"))
      (node (ref "C183") (pin "2") (pinfunction "2_2") (pintype "passive"))
      (node (ref "C184") (pin "1") (pinfunction "1_1") (pintype "passive"))
      (node (ref "C68") (pin "2") (pinfunction "2_2") (pintype "passive"))
      (node (ref "R126") (pin "1") (pinfunction "1_1") (pintype "passive"))
      (node (ref "U22") (pin "20") (pinfunction "VA_20") (pintype "passive"))
      (node (ref "U23") (pin "1") (pinfunction "OUT_1") (pintype "power_in"))
      (node (ref "U24") (pin "8") (pinfunction "VCC_8") (pintype "power_in"))
      (node (ref "U25") (pin "8") (pinfunction "VCC_8") (pintype "power_in"))
      (node (ref "U26") (pin "8") (pinfunction "+V_8") (pintype "power_in"))
      (node (ref "U27") (pin "8") (pinfunction "VCC_8") (pintype "power_in"))
    )
    (net (code "59") (name "VCC_5V0_I2S") (class "Default")
      (node (ref "C165") (pin "2") (pinfunction "2_2") (pintype "passive"))
      (node (ref "C166") (pin "1") (pinfunction "1_1") (pintype "passive"))
      (node (ref "L6") (pin "1") (pinfunction "1_1") (pintype "passive"))
      (node (ref "U22") (pin "9") (pinfunction "VD_9") (pintype "passive"))
    )
    (net (code "60") (name "unconnected-(U22-XTI-Pad2)") (class "Default")
      (node (ref "U22") (pin "2") (pinfunction "XTI_2") (pintype "passive"))
    )
    (net (code "61") (name "unconnected-(U22-XTO-Pad1)") (class "Default")
      (node (ref "U22") (pin "1") (pinfunction "XTO_1") (pintype "passive"))
    )
    (net (code "62") (name "unconnected-(U22-~{AMUTEC}-Pad23)") (class "Default")
      (node (ref "U22") (pin "23") (pinfunction "~{AMUTEC}_23") (pintype "output"))
    )
    (net (code "63") (name "unconnected-(U22-~{BMUTEC}-Pad28)") (class "Default")
      (node (ref "U22") (pin "28") (pinfunction "~{BMUTEC}_28") (pintype "passive"))
    )
    (net (code "64") (name "unconnected-(U23-NC-Pad4)") (class "Default")
      (node (ref "U23") (pin "4") (pinfunction "NC_4") (pintype "passive"))
    )
    (net (code "65") (name "unconnected-(U23-NC-Pad5)") (class "Default")
      (node (ref "U23") (pin "5") (pinfunction "NC_5") (pintype "passive"))
    )
    (net (code "66") (name "unconnected-(U24A-VCC-Pad8)") (class "Default")
      (node (ref "U24") (pin "8") (pinfunction "VCC_8") (pintype "power_in"))
    )
    (net (code "67") (name "unconnected-(U24B-VEE-Pad4)") (class "Default")
      (node (ref "U24") (pin "4") (pinfunction "VEE_4") (pintype "power_in"))
    )
    (net (code "68") (name "unconnected-(U25B-VCC-Pad8)") (class "Default")
      (node (ref "U25") (pin "8") (pinfunction "VCC_8") (pintype "power_in"))
    )
    (net (code "69") (name "unconnected-(U25B-VEE-Pad4)") (class "Default")
      (node (ref "U25") (pin "4") (pinfunction "VEE_4") (pintype "power_in"))
    )
    (net (code "70") (name "unconnected-(U27B-VCC-Pad8)") (class "Default")
      (node (ref "U27") (pin "8") (pinfunction "VCC_8") (pintype "power_in"))
    )
    (net (code "71") (name "unconnected-(U27B-VEE-Pad4)") (class "Default")
      (node (ref "U27") (pin "4") (pinfunction "VEE_4") (pintype "power_in"))
    )
  )
)
